# MineralFire-0_3-smd.net
KiCad netlist of a schematic drawn in EAGLE
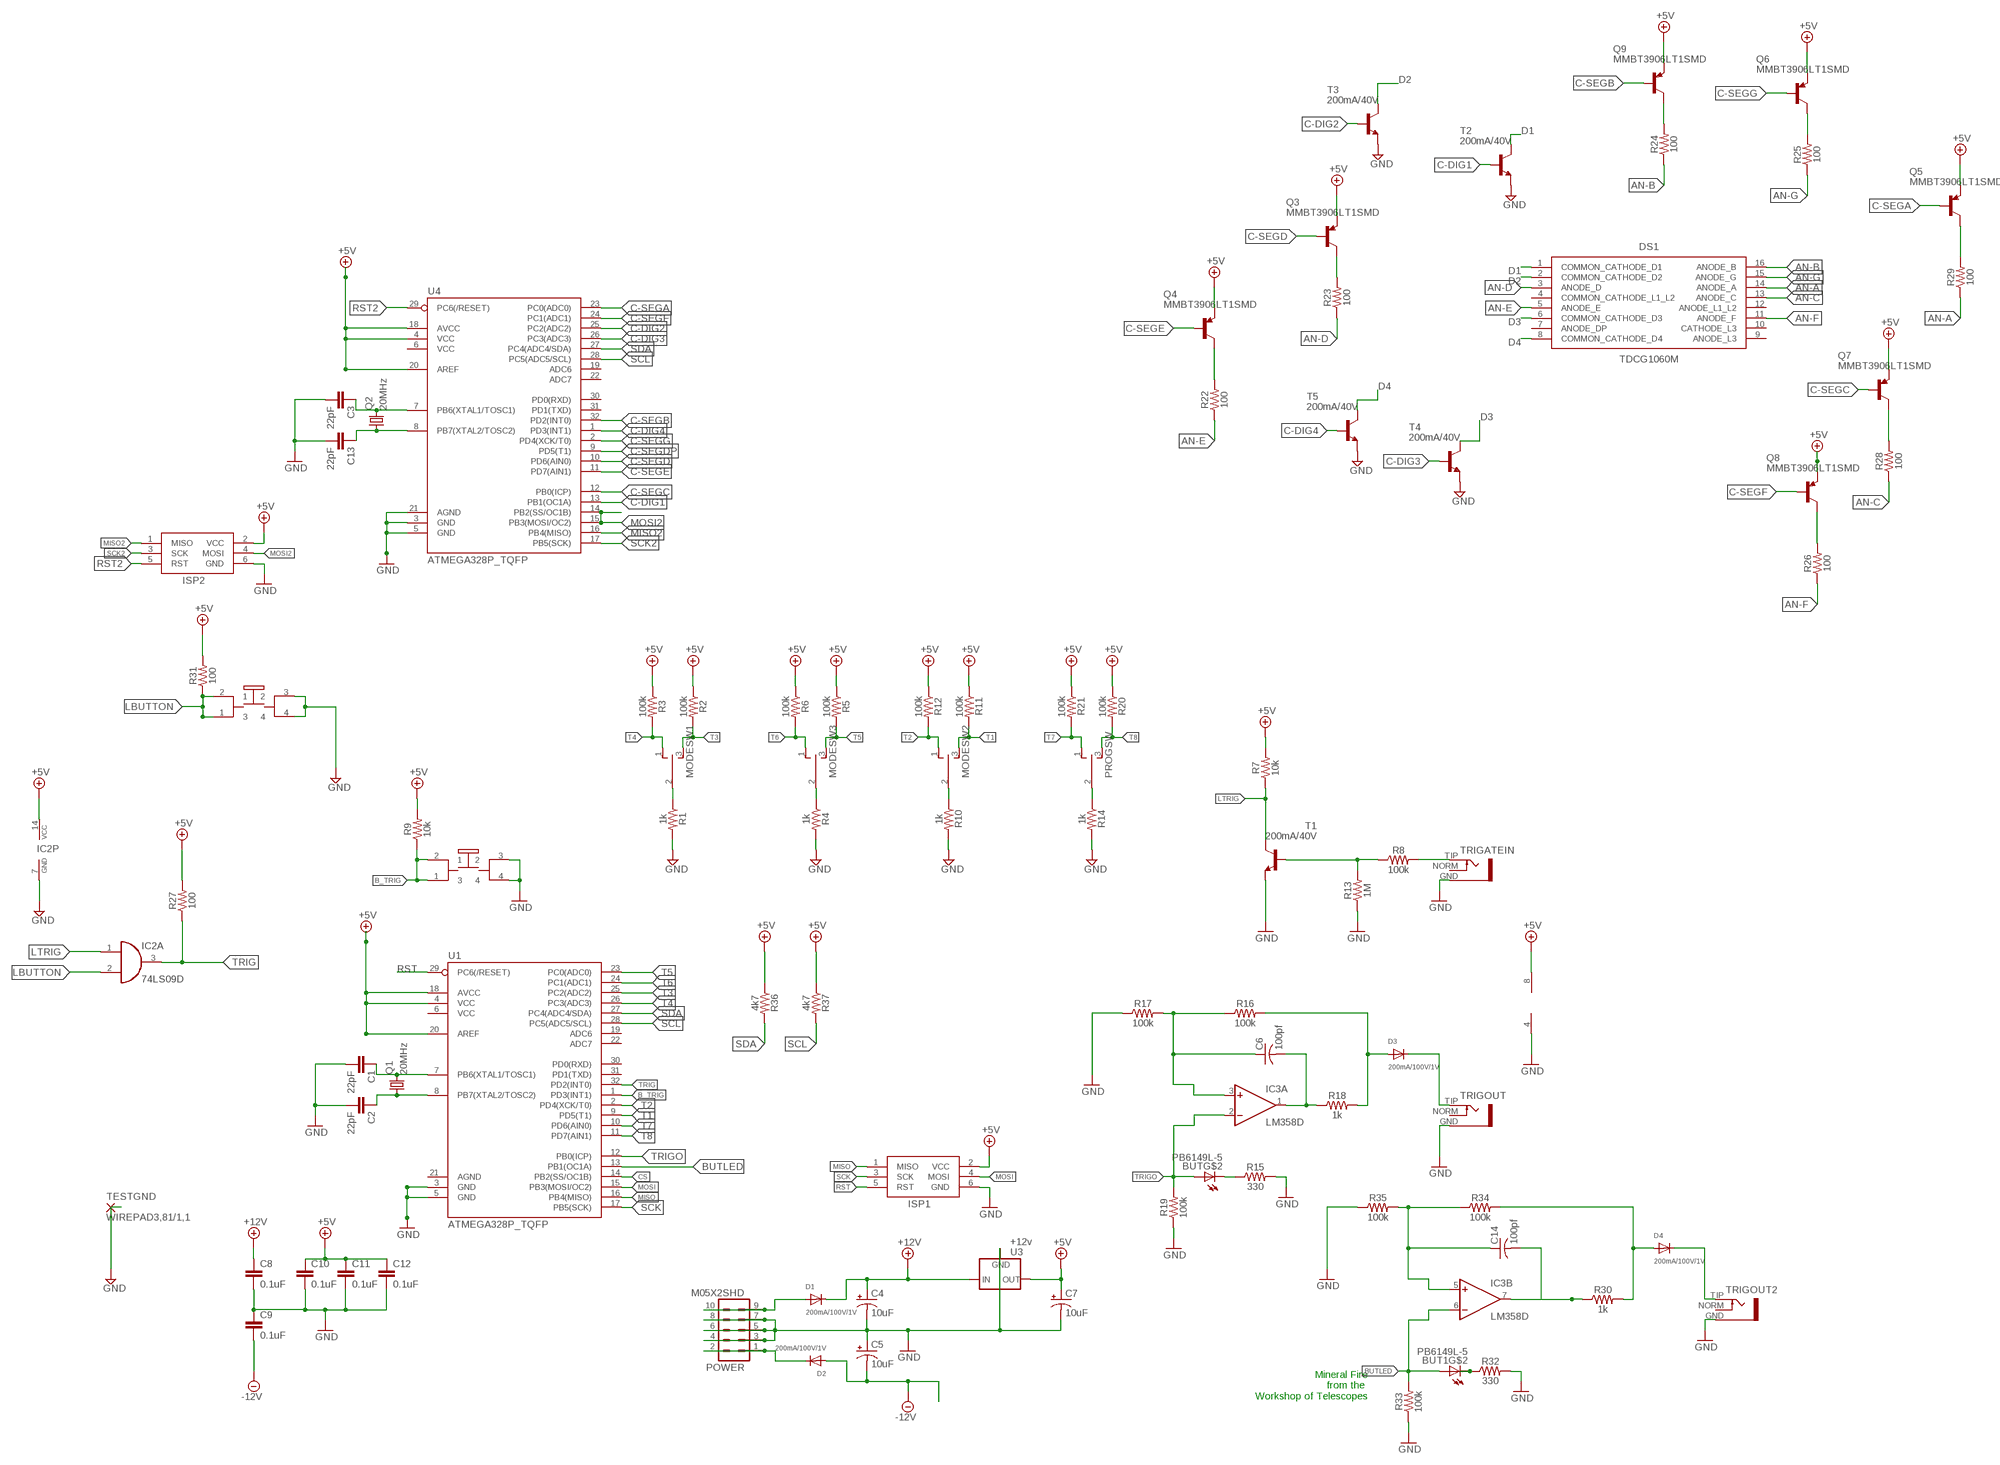
[diagram p0: schematic, sheet 1]

(export (version "E")
  (design (tool "Eeschema 10.0.6"))
  (components
    (comp (ref "BUT")
      (value "PB6149L-5")
      (footprint "eagle-import:PB6149L")
      (libsource (lib "eagle-import") (part "PB6149L-5"))
    )
    (comp (ref "BUT1")
      (value "PB6149L-5")
      (footprint "eagle-import:PB6149L")
      (libsource (lib "eagle-import") (part "PB6149L-5"))
    )
    (comp (ref "C1")
      (value "22pF")
      (footprint "eagle-import:0603")
      (libsource (lib "eagle-import") (part "22PF-0603-50V-5%"))
    )
    (comp (ref "C2")
      (value "22pF")
      (footprint "eagle-import:0603")
      (libsource (lib "eagle-import") (part "22PF-0603-50V-5%"))
    )
    (comp (ref "C3")
      (value "22pF")
      (footprint "eagle-import:0603")
      (libsource (lib "eagle-import") (part "22PF-0603-50V-5%"))
    )
    (comp (ref "C4")
      (value "10uF")
      (footprint "eagle-import:153CLV-0505")
      (libsource (lib "eagle-import") (part "CPOL-US153CLV-0505"))
    )
    (comp (ref "C5")
      (value "10uF")
      (footprint "eagle-import:153CLV-0505")
      (libsource (lib "eagle-import") (part "CPOL-US153CLV-0505"))
    )
    (comp (ref "C6")
      (value "100pf")
      (footprint "eagle-import:C0805K")
      (libsource (lib "eagle-import") (part "C-USC0805K"))
    )
    (comp (ref "C7")
      (value "10uF")
      (footprint "eagle-import:153CLV-0505")
      (libsource (lib "eagle-import") (part "CPOL-US153CLV-0505"))
    )
    (comp (ref "C8")
      (value "0.1uF")
      (footprint "eagle-import:0603")
      (libsource (lib "eagle-import") (part "0.1UF-0603-100V-10%"))
    )
    (comp (ref "C9")
      (value "0.1uF")
      (footprint "eagle-import:0603")
      (libsource (lib "eagle-import") (part "0.1UF-0603-100V-10%"))
    )
    (comp (ref "C10")
      (value "0.1uF")
      (footprint "eagle-import:0603")
      (libsource (lib "eagle-import") (part "0.1UF-0603-100V-10%"))
    )
    (comp (ref "C11")
      (value "0.1uF")
      (footprint "eagle-import:0603")
      (libsource (lib "eagle-import") (part "0.1UF-0603-100V-10%"))
    )
    (comp (ref "C12")
      (value "0.1uF")
      (footprint "eagle-import:0603")
      (libsource (lib "eagle-import") (part "0.1UF-0603-100V-10%"))
    )
    (comp (ref "C13")
      (value "22pF")
      (footprint "eagle-import:0603")
      (libsource (lib "eagle-import") (part "22PF-0603-50V-5%"))
    )
    (comp (ref "C14")
      (value "100pf")
      (footprint "eagle-import:C0805K")
      (libsource (lib "eagle-import") (part "C-USC0805K"))
    )
    (comp (ref "D1")
      (value "200mA/100V/1V")
      (footprint "eagle-import:SMADIODE")
      (libsource (lib "eagle-import") (part "DIODESMA"))
    )
    (comp (ref "D2")
      (value "200mA/100V/1V")
      (footprint "eagle-import:SMADIODE")
      (libsource (lib "eagle-import") (part "DIODESMA"))
    )
    (comp (ref "D3")
      (value "200mA/100V/1V")
      (footprint "eagle-import:SMADIODE")
      (libsource (lib "eagle-import") (part "DIODESMA"))
    )
    (comp (ref "D4")
      (value "200mA/100V/1V")
      (footprint "eagle-import:SMADIODE")
      (libsource (lib "eagle-import") (part "DIODESMA"))
    )
    (comp (ref "DS1")
      (value "TDCG1060M")
      (footprint "eagle-import:DIPS1016W50P254L4020H700Q16N")
      (fields (field (name "RS_PART_NUMBER") "8187530P"))
      (libsource (lib "eagle-import") (part "TDCG1060M"))
    )
    (comp (ref "IC2")
      (value "74LS09D")
      (footprint "eagle-import:SO14")
      (libsource (lib "eagle-import") (part "7409DLS"))
    )
    (comp (ref "IC3")
      (value "LM358D")
      (footprint "eagle-import:SO08")
      (libsource (lib "eagle-import") (part "LM358D"))
    )
    (comp (ref "ISP1")
      (value "AVRISP-6")
      (footprint "eagle-import:AVRISP")
      (libsource (lib "eagle-import") (part "AVRISP-6"))
    )
    (comp (ref "ISP2")
      (value "AVRISP-6")
      (footprint "eagle-import:AVRISP")
      (libsource (lib "eagle-import") (part "AVRISP-6"))
    )
    (comp (ref "MODESW1")
      (value "TOGGLE_ON_OFF_ON")
      (footprint "eagle-import:TOGGLE_ON_OFF_ON")
      (libsource (lib "eagle-import") (part "TOGGLE_ON_OFF_ON"))
    )
    (comp (ref "MODESW2")
      (value "TOGGLE_ON_OFF_ON")
      (footprint "eagle-import:TOGGLE_ON_OFF_ON")
      (libsource (lib "eagle-import") (part "TOGGLE_ON_OFF_ON"))
    )
    (comp (ref "MODESW3")
      (value "TOGGLE_ON_OFF_ON")
      (footprint "eagle-import:TOGGLE_ON_OFF_ON")
      (libsource (lib "eagle-import") (part "TOGGLE_ON_OFF_ON"))
    )
    (comp (ref "POWER")
      (value "M05X2SHD")
      (footprint "eagle-import:2X5-SHROUDED")
      (libsource (lib "eagle-import") (part "M05X2SHD"))
    )
    (comp (ref "PROGSW")
      (value "TOGGLE_ON_OFF_ON")
      (footprint "eagle-import:TOGGLE_ON_OFF_ON")
      (libsource (lib "eagle-import") (part "TOGGLE_ON_OFF_ON"))
    )
    (comp (ref "Q1")
      (value "20MHz")
      (footprint "eagle-import:HC49UP")
      (libsource (lib "eagle-import") (part "CRYSTALHC49UP"))
    )
    (comp (ref "Q2")
      (value "20MHz")
      (footprint "eagle-import:HC49UP")
      (libsource (lib "eagle-import") (part "CRYSTALHC49UP"))
    )
    (comp (ref "Q3")
      (value "MMBT3906LT1SMD")
      (footprint "eagle-import:SOT23-BEC")
      (libsource (lib "eagle-import") (part "MMBT3906SMDLT1"))
    )
    (comp (ref "Q4")
      (value "MMBT3906LT1SMD")
      (footprint "eagle-import:SOT23-BEC")
      (libsource (lib "eagle-import") (part "MMBT3906SMDLT1"))
    )
    (comp (ref "Q5")
      (value "MMBT3906LT1SMD")
      (footprint "eagle-import:SOT23-BEC")
      (libsource (lib "eagle-import") (part "MMBT3906SMDLT1"))
    )
    (comp (ref "Q6")
      (value "MMBT3906LT1SMD")
      (footprint "eagle-import:SOT23-BEC")
      (libsource (lib "eagle-import") (part "MMBT3906SMDLT1"))
    )
    (comp (ref "Q7")
      (value "MMBT3906LT1SMD")
      (footprint "eagle-import:SOT23-BEC")
      (libsource (lib "eagle-import") (part "MMBT3906SMDLT1"))
    )
    (comp (ref "Q8")
      (value "MMBT3906LT1SMD")
      (footprint "eagle-import:SOT23-BEC")
      (libsource (lib "eagle-import") (part "MMBT3906SMDLT1"))
    )
    (comp (ref "Q9")
      (value "MMBT3906LT1SMD")
      (footprint "eagle-import:SOT23-BEC")
      (libsource (lib "eagle-import") (part "MMBT3906SMDLT1"))
    )
    (comp (ref "R1")
      (value "1k")
      (footprint "eagle-import:0603")
      (libsource (lib "eagle-import") (part "1KOHM-0603-1/10W-1%"))
    )
    (comp (ref "R2")
      (value "100k")
      (footprint "eagle-import:0603")
      (libsource (lib "eagle-import") (part "100KOHM-0603-1/10W-1%"))
    )
    (comp (ref "R3")
      (value "100k")
      (footprint "eagle-import:0603")
      (libsource (lib "eagle-import") (part "100KOHM-0603-1/10W-1%"))
    )
    (comp (ref "R4")
      (value "1k")
      (footprint "eagle-import:0603")
      (libsource (lib "eagle-import") (part "1KOHM-0603-1/10W-1%"))
    )
    (comp (ref "R5")
      (value "100k")
      (footprint "eagle-import:0603")
      (libsource (lib "eagle-import") (part "100KOHM-0603-1/10W-1%"))
    )
    (comp (ref "R6")
      (value "100k")
      (footprint "eagle-import:0603")
      (libsource (lib "eagle-import") (part "100KOHM-0603-1/10W-1%"))
    )
    (comp (ref "R7")
      (value "10k")
      (footprint "eagle-import:0603")
      (libsource (lib "eagle-import") (part "10KOHM-0603-1/10W-1%"))
    )
    (comp (ref "R8")
      (value "100k")
      (footprint "eagle-import:0603")
      (libsource (lib "eagle-import") (part "100KOHM-0603-1/10W-1%"))
    )
    (comp (ref "R9")
      (value "10k")
      (footprint "eagle-import:0603")
      (libsource (lib "eagle-import") (part "10KOHM-0603-1/10W-1%"))
    )
    (comp (ref "R10")
      (value "1k")
      (footprint "eagle-import:0603")
      (libsource (lib "eagle-import") (part "1KOHM-0603-1/10W-1%"))
    )
    (comp (ref "R11")
      (value "100k")
      (footprint "eagle-import:0603")
      (libsource (lib "eagle-import") (part "100KOHM-0603-1/10W-1%"))
    )
    (comp (ref "R12")
      (value "100k")
      (footprint "eagle-import:0603")
      (libsource (lib "eagle-import") (part "100KOHM-0603-1/10W-1%"))
    )
    (comp (ref "R13")
      (value "1M")
      (footprint "eagle-import:0603")
      (libsource (lib "eagle-import") (part "1MOHM-0603-1/4W-5%"))
    )
    (comp (ref "R14")
      (value "1k")
      (footprint "eagle-import:0603")
      (libsource (lib "eagle-import") (part "1KOHM-0603-1/10W-1%"))
    )
    (comp (ref "R15")
      (value "330")
      (footprint "eagle-import:0603")
      (libsource (lib "eagle-import") (part "330OHM-0603-1/10W-1%"))
    )
    (comp (ref "R16")
      (value "100k")
      (footprint "eagle-import:0603")
      (libsource (lib "eagle-import") (part "100KOHM-0603-1/10W-1%"))
    )
    (comp (ref "R17")
      (value "100k")
      (footprint "eagle-import:0603")
      (libsource (lib "eagle-import") (part "100KOHM-0603-1/10W-1%"))
    )
    (comp (ref "R18")
      (value "1k")
      (footprint "eagle-import:0603")
      (libsource (lib "eagle-import") (part "1KOHM-0603-1/10W-1%"))
    )
    (comp (ref "R19")
      (value "100k")
      (footprint "eagle-import:0603")
      (libsource (lib "eagle-import") (part "100KOHM-0603-1/10W-1%"))
    )
    (comp (ref "R20")
      (value "100k")
      (footprint "eagle-import:0603")
      (libsource (lib "eagle-import") (part "100KOHM-0603-1/10W-1%"))
    )
    (comp (ref "R21")
      (value "100k")
      (footprint "eagle-import:0603")
      (libsource (lib "eagle-import") (part "100KOHM-0603-1/10W-1%"))
    )
    (comp (ref "R22")
      (value "100")
      (footprint "eagle-import:0603")
      (libsource (lib "eagle-import") (part "100OHM-0603-1/10W-1%"))
    )
    (comp (ref "R23")
      (value "100")
      (footprint "eagle-import:0603")
      (libsource (lib "eagle-import") (part "100OHM-0603-1/10W-1%"))
    )
    (comp (ref "R24")
      (value "100")
      (footprint "eagle-import:0603")
      (libsource (lib "eagle-import") (part "100OHM-0603-1/10W-1%"))
    )
    (comp (ref "R25")
      (value "100")
      (footprint "eagle-import:0603")
      (libsource (lib "eagle-import") (part "100OHM-0603-1/10W-1%"))
    )
    (comp (ref "R26")
      (value "100")
      (footprint "eagle-import:0603")
      (libsource (lib "eagle-import") (part "100OHM-0603-1/10W-1%"))
    )
    (comp (ref "R27")
      (value "100")
      (footprint "eagle-import:0603")
      (libsource (lib "eagle-import") (part "100OHM-0603-1/10W-1%"))
    )
    (comp (ref "R28")
      (value "100")
      (footprint "eagle-import:0603")
      (libsource (lib "eagle-import") (part "100OHM-0603-1/10W-1%"))
    )
    (comp (ref "R29")
      (value "100")
      (footprint "eagle-import:0603")
      (libsource (lib "eagle-import") (part "100OHM-0603-1/10W-1%"))
    )
    (comp (ref "R30")
      (value "1k")
      (footprint "eagle-import:0603")
      (libsource (lib "eagle-import") (part "1KOHM-0603-1/10W-1%"))
    )
    (comp (ref "R31")
      (value "100")
      (footprint "eagle-import:0603")
      (libsource (lib "eagle-import") (part "100OHM-0603-1/10W-1%"))
    )
    (comp (ref "R32")
      (value "330")
      (footprint "eagle-import:0603")
      (libsource (lib "eagle-import") (part "330OHM-0603-1/10W-1%"))
    )
    (comp (ref "R33")
      (value "100k")
      (footprint "eagle-import:0603")
      (libsource (lib "eagle-import") (part "100KOHM-0603-1/10W-1%"))
    )
    (comp (ref "R34")
      (value "100k")
      (footprint "eagle-import:0603")
      (libsource (lib "eagle-import") (part "100KOHM-0603-1/10W-1%"))
    )
    (comp (ref "R35")
      (value "100k")
      (footprint "eagle-import:0603")
      (libsource (lib "eagle-import") (part "100KOHM-0603-1/10W-1%"))
    )
    (comp (ref "R36")
      (value "4k7")
      (footprint "eagle-import:0603")
      (libsource (lib "eagle-import") (part "1KOHM-0603-1/10W-1%"))
    )
    (comp (ref "R37")
      (value "4k7")
      (footprint "eagle-import:0603")
      (libsource (lib "eagle-import") (part "1KOHM-0603-1/10W-1%"))
    )
    (comp (ref "T1")
      (value "200mA/40V")
      (footprint "eagle-import:SOT23-BEC")
      (libsource (lib "eagle-import") (part "-NPN-SOT23-BECMMBT3904LT1"))
    )
    (comp (ref "T2")
      (value "200mA/40V")
      (footprint "eagle-import:SOT23-BEC")
      (libsource (lib "eagle-import") (part "-NPN-SOT23-BECMMBT3904LT1"))
    )
    (comp (ref "T3")
      (value "200mA/40V")
      (footprint "eagle-import:SOT23-BEC")
      (libsource (lib "eagle-import") (part "-NPN-SOT23-BECMMBT3904LT1"))
    )
    (comp (ref "T4")
      (value "200mA/40V")
      (footprint "eagle-import:SOT23-BEC")
      (libsource (lib "eagle-import") (part "-NPN-SOT23-BECMMBT3904LT1"))
    )
    (comp (ref "T5")
      (value "200mA/40V")
      (footprint "eagle-import:SOT23-BEC")
      (libsource (lib "eagle-import") (part "-NPN-SOT23-BECMMBT3904LT1"))
    )
    (comp (ref "TESTGND")
      (value "WIREPAD3,81/1,1")
      (footprint "eagle-import:3,81_1,1")
      (libsource (lib "eagle-import") (part "WIREPAD3,81/1,1"))
    )
    (comp (ref "TRIGATEIN")
      (value "S_JACK")
      (footprint "eagle-import:S_JACK")
      (libsource (lib "eagle-import") (part "S_JACK"))
    )
    (comp (ref "TRIGOUT")
      (value "S_JACK")
      (footprint "eagle-import:S_JACK")
      (libsource (lib "eagle-import") (part "S_JACK"))
    )
    (comp (ref "TRIGOUT2")
      (value "S_JACK")
      (footprint "eagle-import:S_JACK")
      (libsource (lib "eagle-import") (part "S_JACK"))
    )
    (comp (ref "U1")
      (value "ATMEGA328P_TQFP")
      (footprint "eagle-import:TQFP32-08")
      (libsource (lib "eagle-import") (part "ATMEGA328P_TQFP"))
    )
    (comp (ref "U3")
      (value "+12v")
      (footprint "eagle-import:TO-252")
      (libsource (lib "eagle-import") (part "V_REG_78XX7812"))
    )
    (comp (ref "U4")
      (value "ATMEGA328P_TQFP")
      (footprint "eagle-import:TQFP32-08")
      (libsource (lib "eagle-import") (part "ATMEGA328P_TQFP"))
    )
  )
  (nets
    (net (code "1") (name "+5V") (class "Default")
      (node (ref "C10") (pin "1") (pinfunction "1_1") (pintype "passive"))
      (node (ref "C11") (pin "1") (pinfunction "1_1") (pintype "passive"))
      (node (ref "C12") (pin "1") (pinfunction "1_1") (pintype "passive"))
      (node (ref "C7") (pin "+") (pinfunction "+_+") (pintype "passive"))
      (node (ref "IC2") (pin "14") (pinfunction "VCC_14") (pintype "power_in"))
      (node (ref "IC3") (pin "8") (pinfunction "V+_8") (pintype "power_in"))
      (node (ref "ISP1") (pin "2") (pinfunction "VCC_2") (pintype "power_in"))
      (node (ref "ISP2") (pin "2") (pinfunction "VCC_2") (pintype "power_in"))
      (node (ref "Q3") (pin "E") (pinfunction "E_E") (pintype "passive"))
      (node (ref "Q4") (pin "E") (pinfunction "E_E") (pintype "passive"))
      (node (ref "Q5") (pin "E") (pinfunction "E_E") (pintype "passive"))
      (node (ref "Q6") (pin "E") (pinfunction "E_E") (pintype "passive"))
      (node (ref "Q7") (pin "E") (pinfunction "E_E") (pintype "passive"))
      (node (ref "Q8") (pin "E") (pinfunction "E_E") (pintype "passive"))
      (node (ref "Q9") (pin "E") (pinfunction "E_E") (pintype "passive"))
      (node (ref "R11") (pin "1") (pinfunction "1_1") (pintype "passive"))
      (node (ref "R12") (pin "1") (pinfunction "1_1") (pintype "passive"))
      (node (ref "R2") (pin "1") (pinfunction "1_1") (pintype "passive"))
      (node (ref "R20") (pin "1") (pinfunction "1_1") (pintype "passive"))
      (node (ref "R21") (pin "1") (pinfunction "1_1") (pintype "passive"))
      (node (ref "R27") (pin "2") (pinfunction "2_2") (pintype "passive"))
      (node (ref "R3") (pin "1") (pinfunction "1_1") (pintype "passive"))
      (node (ref "R31") (pin "2") (pinfunction "2_2") (pintype "passive"))
      (node (ref "R36") (pin "1") (pinfunction "1_1") (pintype "passive"))
      (node (ref "R37") (pin "1") (pinfunction "1_1") (pintype "passive"))
      (node (ref "R5") (pin "1") (pinfunction "1_1") (pintype "passive"))
      (node (ref "R6") (pin "1") (pinfunction "1_1") (pintype "passive"))
      (node (ref "R7") (pin "2") (pinfunction "2_2") (pintype "passive"))
      (node (ref "R9") (pin "2") (pinfunction "2_2") (pintype "passive"))
      (node (ref "U1") (pin "18") (pinfunction "AVCC_18") (pintype "bidirectional"))
      (node (ref "U1") (pin "20") (pinfunction "AREF_20") (pintype "bidirectional"))
      (node (ref "U1") (pin "4") (pinfunction "VCC_4") (pintype "bidirectional"))
      (node (ref "U3") (pin "2") (pinfunction "OUT_2") (pintype "passive"))
      (node (ref "U4") (pin "18") (pinfunction "AVCC_18") (pintype "bidirectional"))
      (node (ref "U4") (pin "20") (pinfunction "AREF_20") (pintype "bidirectional"))
      (node (ref "U4") (pin "4") (pinfunction "VCC_4") (pintype "bidirectional"))
    )
    (net (code "2") (name "+12V") (class "Default")
      (node (ref "C4") (pin "+") (pinfunction "+_+") (pintype "passive"))
      (node (ref "C8") (pin "1") (pinfunction "1_1") (pintype "passive"))
      (node (ref "D1") (pin "C") (pinfunction "C_C") (pintype "passive"))
      (node (ref "U3") (pin "1") (pinfunction "IN_1") (pintype "input"))
    )
    (net (code "3") (name "-12V") (class "Default")
      (node (ref "C5") (pin "-") (pinfunction "-_-") (pintype "passive"))
      (node (ref "C9") (pin "2") (pinfunction "2_2") (pintype "passive"))
      (node (ref "D2") (pin "A") (pinfunction "A_A") (pintype "passive"))
    )
    (net (code "4") (name "/D1") (class "Default")
      (node (ref "DS1") (pin "1") (pinfunction "COMMON_CATHODE_D1_1") (pintype "input"))
      (node (ref "T2") (pin "C") (pinfunction "C_C") (pintype "passive"))
    )
    (net (code "5") (name "/D2") (class "Default")
      (node (ref "DS1") (pin "2") (pinfunction "COMMON_CATHODE_D2_2") (pintype "input"))
      (node (ref "T3") (pin "C") (pinfunction "C_C") (pintype "passive"))
    )
    (net (code "6") (name "/D3") (class "Default")
      (node (ref "DS1") (pin "6") (pinfunction "COMMON_CATHODE_D3_6") (pintype "input"))
      (node (ref "T4") (pin "C") (pinfunction "C_C") (pintype "passive"))
    )
    (net (code "7") (name "/D4") (class "Default")
      (node (ref "DS1") (pin "8") (pinfunction "COMMON_CATHODE_D4_8") (pintype "input"))
      (node (ref "T5") (pin "C") (pinfunction "C_C") (pintype "passive"))
    )
    (net (code "8") (name "AN-A") (class "Default")
      (node (ref "DS1") (pin "14") (pinfunction "ANODE_A_14") (pintype "input"))
      (node (ref "R29") (pin "1") (pinfunction "1_1") (pintype "passive"))
    )
    (net (code "9") (name "AN-B") (class "Default")
      (node (ref "DS1") (pin "16") (pinfunction "ANODE_B_16") (pintype "input"))
      (node (ref "R24") (pin "1") (pinfunction "1_1") (pintype "passive"))
    )
    (net (code "10") (name "AN-C") (class "Default")
      (node (ref "DS1") (pin "13") (pinfunction "ANODE_C_13") (pintype "input"))
      (node (ref "R28") (pin "1") (pinfunction "1_1") (pintype "passive"))
    )
    (net (code "11") (name "AN-D") (class "Default")
      (node (ref "DS1") (pin "3") (pinfunction "ANODE_D_3") (pintype "input"))
      (node (ref "R23") (pin "1") (pinfunction "1_1") (pintype "passive"))
    )
    (net (code "12") (name "AN-E") (class "Default")
      (node (ref "DS1") (pin "5") (pinfunction "ANODE_E_5") (pintype "input"))
      (node (ref "R22") (pin "1") (pinfunction "1_1") (pintype "passive"))
    )
    (net (code "13") (name "AN-F") (class "Default")
      (node (ref "DS1") (pin "11") (pinfunction "ANODE_F_11") (pintype "input"))
      (node (ref "R26") (pin "1") (pinfunction "1_1") (pintype "passive"))
    )
    (net (code "14") (name "AN-G") (class "Default")
      (node (ref "DS1") (pin "15") (pinfunction "ANODE_G_15") (pintype "input"))
      (node (ref "R25") (pin "1") (pinfunction "1_1") (pintype "passive"))
    )
    (net (code "15") (name "BUTLED") (class "Default")
      (node (ref "BUT1") (pin "A") (pinfunction "A_A") (pintype "passive"))
      (node (ref "IC3") (pin "6") (pinfunction "-IN_6") (pintype "input"))
      (node (ref "R33") (pin "2") (pinfunction "2_2") (pintype "passive"))
      (node (ref "U1") (pin "13") (pinfunction "PB1(OC1A)_13") (pintype "bidirectional"))
    )
    (net (code "16") (name "B_TRIG") (class "Default")
      (node (ref "BUT") (pin "1") (pinfunction "3_1") (pintype "bidirectional"))
      (node (ref "BUT") (pin "2") (pinfunction "1_2") (pintype "bidirectional"))
      (node (ref "R9") (pin "1") (pinfunction "1_1") (pintype "passive"))
      (node (ref "U1") (pin "1") (pinfunction "PD3(INT1)_1") (pintype "bidirectional"))
    )
    (net (code "17") (name "C-DIG1") (class "Default")
      (node (ref "T2") (pin "B") (pinfunction "B_B") (pintype "passive"))
      (node (ref "U4") (pin "13") (pinfunction "PB1(OC1A)_13") (pintype "bidirectional"))
    )
    (net (code "18") (name "C-DIG2") (class "Default")
      (node (ref "T3") (pin "B") (pinfunction "B_B") (pintype "passive"))
      (node (ref "U4") (pin "25") (pinfunction "PC2(ADC2)_25") (pintype "bidirectional"))
    )
    (net (code "19") (name "C-DIG3") (class "Default")
      (node (ref "T4") (pin "B") (pinfunction "B_B") (pintype "passive"))
      (node (ref "U4") (pin "26") (pinfunction "PC3(ADC3)_26") (pintype "bidirectional"))
    )
    (net (code "20") (name "C-DIG4") (class "Default")
      (node (ref "T5") (pin "B") (pinfunction "B_B") (pintype "passive"))
      (node (ref "U4") (pin "1") (pinfunction "PD3(INT1)_1") (pintype "bidirectional"))
    )
    (net (code "21") (name "C-SEGA") (class "Default")
      (node (ref "Q5") (pin "B") (pinfunction "B_B") (pintype "passive"))
      (node (ref "U4") (pin "23") (pinfunction "PC0(ADC0)_23") (pintype "bidirectional"))
    )
    (net (code "22") (name "C-SEGB") (class "Default")
      (node (ref "Q9") (pin "B") (pinfunction "B_B") (pintype "passive"))
      (node (ref "U4") (pin "32") (pinfunction "PD2(INT0)_32") (pintype "bidirectional"))
    )
    (net (code "23") (name "C-SEGC") (class "Default")
      (node (ref "Q7") (pin "B") (pinfunction "B_B") (pintype "passive"))
      (node (ref "U4") (pin "12") (pinfunction "PB0(ICP)_12") (pintype "bidirectional"))
    )
    (net (code "24") (name "C-SEGD") (class "Default")
      (node (ref "Q3") (pin "B") (pinfunction "B_B") (pintype "passive"))
      (node (ref "U4") (pin "10") (pinfunction "PD6(AIN0)_10") (pintype "bidirectional"))
    )
    (net (code "25") (name "C-SEGDP") (class "Default")
      (node (ref "U4") (pin "9") (pinfunction "PD5(T1)_9") (pintype "bidirectional"))
    )
    (net (code "26") (name "C-SEGE") (class "Default")
      (node (ref "Q4") (pin "B") (pinfunction "B_B") (pintype "passive"))
      (node (ref "U4") (pin "11") (pinfunction "PD7(AIN1)_11") (pintype "bidirectional"))
    )
    (net (code "27") (name "C-SEGF") (class "Default")
      (node (ref "Q8") (pin "B") (pinfunction "B_B") (pintype "passive"))
      (node (ref "U4") (pin "24") (pinfunction "PC1(ADC1)_24") (pintype "bidirectional"))
    )
    (net (code "28") (name "C-SEGG") (class "Default")
      (node (ref "Q6") (pin "B") (pinfunction "B_B") (pintype "passive"))
      (node (ref "U4") (pin "2") (pinfunction "PD4(XCK/T0)_2") (pintype "bidirectional"))
    )
    (net (code "29") (name "CS") (class "Default")
      (node (ref "U1") (pin "14") (pinfunction "PB2(SS/OC1B)_14") (pintype "bidirectional"))
    )
    (net (code "30") (name "GND") (class "Default")
      (node (ref "BUT") (pin "3") (pinfunction "2_3") (pintype "bidirectional"))
      (node (ref "BUT") (pin "4") (pinfunction "4_4") (pintype "bidirectional"))
      (node (ref "BUT1") (pin "3") (pinfunction "2_3") (pintype "bidirectional"))
      (node (ref "BUT1") (pin "4") (pinfunction "4_4") (pintype "bidirectional"))
      (node (ref "C1") (pin "2") (pinfunction "2_2") (pintype "passive"))
      (node (ref "C10") (pin "2") (pinfunction "2_2") (pintype "passive"))
      (node (ref "C11") (pin "2") (pinfunction "2_2") (pintype "passive"))
      (node (ref "C12") (pin "2") (pinfunction "2_2") (pintype "passive"))
      (node (ref "C13") (pin "2") (pinfunction "2_2") (pintype "passive"))
      (node (ref "C2") (pin "2") (pinfunction "2_2") (pintype "passive"))
      (node (ref "C3") (pin "2") (pinfunction "2_2") (pintype "passive"))
      (node (ref "C4") (pin "-") (pinfunction "-_-") (pintype "passive"))
      (node (ref "C5") (pin "+") (pinfunction "+_+") (pintype "passive"))
      (node (ref "C7") (pin "-") (pinfunction "-_-") (pintype "passive"))
      (node (ref "C8") (pin "2") (pinfunction "2_2") (pintype "passive"))
      (node (ref "C9") (pin "1") (pinfunction "1_1") (pintype "passive"))
      (node (ref "IC2") (pin "7") (pinfunction "GND_7") (pintype "power_in"))
      (node (ref "IC3") (pin "4") (pinfunction "V-_4") (pintype "power_in"))
      (node (ref "ISP1") (pin "6") (pinfunction "GND_6") (pintype "power_in"))
      (node (ref "ISP2") (pin "6") (pinfunction "GND_6") (pintype "power_in"))
      (node (ref "POWER") (pin "3") (pinfunction "3_3") (pintype "passive"))
      (node (ref "POWER") (pin "4") (pinfunction "4_4") (pintype "passive"))
      (node (ref "POWER") (pin "5") (pinfunction "5_5") (pintype "passive"))
      (node (ref "POWER") (pin "6") (pinfunction "6_6") (pintype "passive"))
      (node (ref "POWER") (pin "7") (pinfunction "7_7") (pintype "passive"))
      (node (ref "POWER") (pin "8") (pinfunction "8_8") (pintype "passive"))
      (node (ref "R1") (pin "2") (pinfunction "2_2") (pintype "passive"))
      (node (ref "R10") (pin "2") (pinfunction "2_2") (pintype "passive"))
      (node (ref "R13") (pin "1") (pinfunction "1_1") (pintype "passive"))
      (node (ref "R14") (pin "2") (pinfunction "2_2") (pintype "passive"))
      (node (ref "R15") (pin "2") (pinfunction "2_2") (pintype "passive"))
      (node (ref "R17") (pin "1") (pinfunction "1_1") (pintype "passive"))
      (node (ref "R19") (pin "1") (pinfunction "1_1") (pintype "passive"))
      (node (ref "R32") (pin "2") (pinfunction "2_2") (pintype "passive"))
      (node (ref "R33") (pin "1") (pinfunction "1_1") (pintype "passive"))
      (node (ref "R35") (pin "1") (pinfunction "1_1") (pintype "passive"))
      (node (ref "R4") (pin "2") (pinfunction "2_2") (pintype "passive"))
      (node (ref "T1") (pin "E") (pinfunction "E_E") (pintype "passive"))
      (node (ref "T2") (pin "E") (pinfunction "E_E") (pintype "passive"))
      (node (ref "T3") (pin "E") (pinfunction "E_E") (pintype "passive"))
      (node (ref "T4") (pin "E") (pinfunction "E_E") (pintype "passive"))
      (node (ref "T5") (pin "E") (pinfunction "E_E") (pintype "passive"))
      (node (ref "TESTGND") (pin "1") (pinfunction "P_1") (pintype "passive"))
      (node (ref "TRIGATEIN") (pin "GND") (pinfunction "GND_GND") (pintype "passive"))
      (node (ref "TRIGOUT") (pin "GND") (pinfunction "GND_GND") (pintype "passive"))
      (node (ref "TRIGOUT2") (pin "GND") (pinfunction "GND_GND") (pintype "passive"))
      (node (ref "U1") (pin "3") (pinfunction "GND_3") (pintype "bidirectional"))
      (node (ref "U1") (pin "5") (pinfunction "GND_5") (pintype "bidirectional"))
      (node (ref "U3") (pin "3") (pinfunction "GND_3") (pintype "input"))
      (node (ref "U4") (pin "21") (pinfunction "AGND_21") (pintype "bidirectional"))
      (node (ref "U4") (pin "3") (pinfunction "GND_3") (pintype "bidirectional"))
      (node (ref "U4") (pin "5") (pinfunction "GND_5") (pintype "bidirectional"))
    )
    (net (code "31") (name "LBUTTON") (class "Default")
      (node (ref "BUT1") (pin "1") (pinfunction "3_1") (pintype "bidirectional"))
      (node (ref "BUT1") (pin "2") (pinfunction "1_2") (pintype "bidirectional"))
      (node (ref "IC2") (pin "2") (pinfunction "I1_2") (pintype "input"))
      (node (ref "R31") (pin "1") (pinfunction "1_1") (pintype "passive"))
    )
    (net (code "32") (name "LTRIG") (class "Default")
      (node (ref "IC2") (pin "1") (pinfunction "I0_1") (pintype "input"))
      (node (ref "R7") (pin "1") (pinfunction "1_1") (pintype "passive"))
      (node (ref "T1") (pin "C") (pinfunction "C_C") (pintype "passive"))
    )
    (net (code "33") (name "MISO") (class "Default")
      (node (ref "ISP1") (pin "1") (pinfunction "MISO_1") (pintype "input"))
      (node (ref "U1") (pin "16") (pinfunction "PB4(MISO)_16") (pintype "bidirectional"))
    )
    (net (code "34") (name "MISO2") (class "Default")
      (node (ref "ISP2") (pin "1") (pinfunction "MISO_1") (pintype "input"))
      (node (ref "U4") (pin "16") (pinfunction "PB4(MISO)_16") (pintype "bidirectional"))
    )
    (net (code "35") (name "MOSI") (class "Default")
      (node (ref "ISP1") (pin "4") (pinfunction "MOSI_4") (pintype "output"))
      (node (ref "U1") (pin "15") (pinfunction "PB3(MOSI/OC2)_15") (pintype "bidirectional"))
    )
    (net (code "36") (name "MOSI2") (class "Default")
      (node (ref "ISP2") (pin "4") (pinfunction "MOSI_4") (pintype "output"))
      (node (ref "U4") (pin "14") (pinfunction "PB2(SS/OC1B)_14") (pintype "bidirectional"))
      (node (ref "U4") (pin "15") (pinfunction "PB3(MOSI/OC2)_15") (pintype "bidirectional"))
    )
    (net (code "37") (name "Net-(BUT1B-C)") (class "Default")
      (node (ref "BUT1") (pin "K") (pinfunction "C_K") (pintype "passive"))
      (node (ref "R32") (pin "1") (pinfunction "1_1") (pintype "passive"))
    )
    (net (code "38") (name "Net-(BUTB-C)") (class "Default")
      (node (ref "BUT") (pin "K") (pinfunction "C_K") (pintype "passive"))
      (node (ref "R15") (pin "1") (pinfunction "1_1") (pintype "passive"))
    )
    (net (code "39") (name "Net-(D1-PadA)") (class "Default")
      (node (ref "D1") (pin "A") (pinfunction "A_A") (pintype "passive"))
      (node (ref "POWER") (pin "10") (pinfunction "10_10") (pintype "passive"))
      (node (ref "POWER") (pin "9") (pinfunction "9_9") (pintype "passive"))
    )
    (net (code "40") (name "Net-(D2-PadC)") (class "Default")
      (node (ref "D2") (pin "C") (pinfunction "C_C") (pintype "passive"))
      (node (ref "POWER") (pin "1") (pinfunction "1_1") (pintype "passive"))
      (node (ref "POWER") (pin "2") (pinfunction "2_2") (pintype "passive"))
    )
    (net (code "41") (name "Net-(D3-PadA)") (class "Default")
      (node (ref "D3") (pin "A") (pinfunction "A_A") (pintype "passive"))
      (node (ref "R16") (pin "2") (pinfunction "2_2") (pintype "passive"))
      (node (ref "R18") (pin "2") (pinfunction "2_2") (pintype "passive"))
    )
    (net (code "42") (name "Net-(D3-PadC)") (class "Default")
      (node (ref "D3") (pin "C") (pinfunction "C_C") (pintype "passive"))
      (node (ref "TRIGOUT") (pin "TIP") (pinfunction "TIP_TIP") (pintype "passive"))
    )
    (net (code "43") (name "Net-(D4-PadA)") (class "Default")
      (node (ref "D4") (pin "A") (pinfunction "A_A") (pintype "passive"))
      (node (ref "R30") (pin "2") (pinfunction "2_2") (pintype "passive"))
    )
    (net (code "44") (name "Net-(D4-PadC)") (class "Default")
      (node (ref "D4") (pin "C") (pinfunction "C_C") (pintype "passive"))
      (node (ref "TRIGOUT2") (pin "TIP") (pinfunction "TIP_TIP") (pintype "passive"))
    )
    (net (code "45") (name "Net-(IC3A-+IN)") (class "Default")
      (node (ref "C6") (pin "1") (pinfunction "1_1") (pintype "passive"))
      (node (ref "IC3") (pin "3") (pinfunction "+IN_3") (pintype "input"))
      (node (ref "R16") (pin "1") (pinfunction "1_1") (pintype "passive"))
      (node (ref "R17") (pin "2") (pinfunction "2_2") (pintype "passive"))
    )
    (net (code "46") (name "Net-(IC3A-OUT)") (class "Default")
      (node (ref "C6") (pin "2") (pinfunction "2_2") (pintype "passive"))
      (node (ref "IC3") (pin "1") (pinfunction "OUT_1") (pintype "output"))
      (node (ref "R18") (pin "1") (pinfunction "1_1") (pintype "passive"))
    )
    (net (code "47") (name "Net-(IC3B-+IN)") (class "Default")
      (node (ref "C14") (pin "1") (pinfunction "1_1") (pintype "passive"))
      (node (ref "IC3") (pin "5") (pinfunction "+IN_5") (pintype "input"))
      (node (ref "R34") (pin "1") (pinfunction "1_1") (pintype "passive"))
      (node (ref "R35") (pin "2") (pinfunction "2_2") (pintype "passive"))
    )
    (net (code "48") (name "Net-(IC3B-OUT)") (class "Default")
      (node (ref "IC3") (pin "7") (pinfunction "OUT_7") (pintype "output"))
      (node (ref "R30") (pin "1") (pinfunction "1_1") (pintype "passive"))
    )
    (net (code "49") (name "Net-(MODESW1-P)") (class "Default")
      (node (ref "MODESW1") (pin "2") (pinfunction "P_2") (pintype "passive"))
      (node (ref "R1") (pin "1") (pinfunction "1_1") (pintype "passive"))
    )
    (net (code "50") (name "Net-(MODESW2-P)") (class "Default")
      (node (ref "MODESW2") (pin "2") (pinfunction "P_2") (pintype "passive"))
      (node (ref "R10") (pin "1") (pinfunction "1_1") (pintype "passive"))
    )
    (net (code "51") (name "Net-(MODESW3-P)") (class "Default")
      (node (ref "MODESW3") (pin "2") (pinfunction "P_2") (pintype "passive"))
      (node (ref "R4") (pin "1") (pinfunction "1_1") (pintype "passive"))
    )
    (net (code "52") (name "Net-(PROGSW-P)") (class "Default")
      (node (ref "PROGSW") (pin "2") (pinfunction "P_2") (pintype "passive"))
      (node (ref "R14") (pin "1") (pinfunction "1_1") (pintype "passive"))
    )
    (net (code "53") (name "Net-(Q3-PadC)") (class "Default")
      (node (ref "Q3") (pin "C") (pinfunction "C_C") (pintype "passive"))
      (node (ref "R23") (pin "2") (pinfunction "2_2") (pintype "passive"))
    )
    (net (code "54") (name "Net-(Q4-PadC)") (class "Default")
      (node (ref "Q4") (pin "C") (pinfunction "C_C") (pintype "passive"))
      (node (ref "R22") (pin "2") (pinfunction "2_2") (pintype "passive"))
    )
    (net (code "55") (name "Net-(Q5-PadC)") (class "Default")
      (node (ref "Q5") (pin "C") (pinfunction "C_C") (pintype "passive"))
      (node (ref "R29") (pin "2") (pinfunction "2_2") (pintype "passive"))
    )
    (net (code "56") (name "Net-(Q6-PadC)") (class "Default")
      (node (ref "Q6") (pin "C") (pinfunction "C_C") (pintype "passive"))
      (node (ref "R25") (pin "2") (pinfunction "2_2") (pintype "passive"))
    )
    (net (code "57") (name "Net-(Q7-PadC)") (class "Default")
      (node (ref "Q7") (pin "C") (pinfunction "C_C") (pintype "passive"))
      (node (ref "R28") (pin "2") (pinfunction "2_2") (pintype "passive"))
    )
    (net (code "58") (name "Net-(Q8-PadC)") (class "Default")
      (node (ref "Q8") (pin "C") (pinfunction "C_C") (pintype "passive"))
      (node (ref "R26") (pin "2") (pinfunction "2_2") (pintype "passive"))
    )
    (net (code "59") (name "Net-(Q9-PadC)") (class "Default")
      (node (ref "Q9") (pin "C") (pinfunction "C_C") (pintype "passive"))
      (node (ref "R24") (pin "2") (pinfunction "2_2") (pintype "passive"))
    )
    (net (code "60") (name "Net-(R8-Pad2)") (class "Default")
      (node (ref "R8") (pin "2") (pinfunction "2_2") (pintype "passive"))
      (node (ref "TRIGATEIN") (pin "TIP") (pinfunction "TIP_TIP") (pintype "passive"))
    )
    (net (code "61") (name "Net-(R13-Pad2)") (class "Default")
      (node (ref "R13") (pin "2") (pinfunction "2_2") (pintype "passive"))
      (node (ref "R8") (pin "1") (pinfunction "1_1") (pintype "passive"))
      (node (ref "T1") (pin "B") (pinfunction "B_B") (pintype "passive"))
    )
    (net (code "62") (name "Net-(U1-PB6(XTAL1{slash}TOSC1))") (class "Default")
      (node (ref "C1") (pin "1") (pinfunction "1_1") (pintype "passive"))
      (node (ref "Q1") (pin "2") (pinfunction "2_2") (pintype "passive"))
      (node (ref "U1") (pin "7") (pinfunction "PB6(XTAL1/TOSC1)_7") (pintype "bidirectional"))
    )
    (net (code "63") (name "Net-(U1-PB7(XTAL2{slash}TOSC2))") (class "Default")
      (node (ref "C2") (pin "1") (pinfunction "1_1") (pintype "passive"))
      (node (ref "Q1") (pin "1") (pinfunction "1_1") (pintype "passive"))
      (node (ref "U1") (pin "8") (pinfunction "PB7(XTAL2/TOSC2)_8") (pintype "bidirectional"))
    )
    (net (code "64") (name "Net-(U4-PB6(XTAL1{slash}TOSC1))") (class "Default")
      (node (ref "C3") (pin "1") (pinfunction "1_1") (pintype "passive"))
      (node (ref "Q2") (pin "2") (pinfunction "2_2") (pintype "passive"))
      (node (ref "U4") (pin "7") (pinfunction "PB6(XTAL1/TOSC1)_7") (pintype "bidirectional"))
    )
    (net (code "65") (name "Net-(U4-PB7(XTAL2{slash}TOSC2))") (class "Default")
      (node (ref "C13") (pin "1") (pinfunction "1_1") (pintype "passive"))
      (node (ref "Q2") (pin "1") (pinfunction "1_1") (pintype "passive"))
      (node (ref "U4") (pin "8") (pinfunction "PB7(XTAL2/TOSC2)_8") (pintype "bidirectional"))
    )
    (net (code "66") (name "RST") (class "Default")
      (node (ref "ISP1") (pin "5") (pinfunction "RST_5") (pintype "output"))
      (node (ref "U1") (pin "29") (pinfunction "PC6(/RESET)_29") (pintype "bidirectional"))
    )
    (net (code "67") (name "RST2") (class "Default")
      (node (ref "ISP2") (pin "5") (pinfunction "RST_5") (pintype "output"))
      (node (ref "U4") (pin "29") (pinfunction "PC6(/RESET)_29") (pintype "bidirectional"))
    )
    (net (code "68") (name "SCK") (class "Default")
      (node (ref "ISP1") (pin "3") (pinfunction "SCK_3") (pintype "output"))
      (node (ref "U1") (pin "17") (pinfunction "PB5(SCK)_17") (pintype "bidirectional"))
    )
    (net (code "69") (name "SCK2") (class "Default")
      (node (ref "ISP2") (pin "3") (pinfunction "SCK_3") (pintype "output"))
      (node (ref "U4") (pin "17") (pinfunction "PB5(SCK)_17") (pintype "bidirectional"))
    )
    (net (code "70") (name "SCL") (class "Default")
      (node (ref "R37") (pin "2") (pinfunction "2_2") (pintype "passive"))
      (node (ref "U1") (pin "28") (pinfunction "PC5(ADC5/SCL)_28") (pintype "bidirectional"))
      (node (ref "U4") (pin "28") (pinfunction "PC5(ADC5/SCL)_28") (pintype "bidirectional"))
    )
    (net (code "71") (name "SDA") (class "Default")
      (node (ref "R36") (pin "2") (pinfunction "2_2") (pintype "passive"))
      (node (ref "U1") (pin "27") (pinfunction "PC4(ADC4/SDA)_27") (pintype "bidirectional"))
      (node (ref "U4") (pin "27") (pinfunction "PC4(ADC4/SDA)_27") (pintype "bidirectional"))
    )
    (net (code "72") (name "T1") (class "Default")
      (node (ref "MODESW2") (pin "3") (pinfunction "S_3") (pintype "passive"))
      (node (ref "R11") (pin "2") (pinfunction "2_2") (pintype "passive"))
      (node (ref "U1") (pin "9") (pinfunction "PD5(T1)_9") (pintype "bidirectional"))
    )
    (net (code "73") (name "T2") (class "Default")
      (node (ref "MODESW2") (pin "1") (pinfunction "O_1") (pintype "passive"))
      (node (ref "R12") (pin "2") (pinfunction "2_2") (pintype "passive"))
      (node (ref "U1") (pin "2") (pinfunction "PD4(XCK/T0)_2") (pintype "bidirectional"))
    )
    (net (code "74") (name "T3") (class "Default")
      (node (ref "MODESW1") (pin "3") (pinfunction "S_3") (pintype "passive"))
      (node (ref "R2") (pin "2") (pinfunction "2_2") (pintype "passive"))
      (node (ref "U1") (pin "25") (pinfunction "PC2(ADC2)_25") (pintype "bidirectional"))
    )
    (net (code "75") (name "T4") (class "Default")
      (node (ref "MODESW1") (pin "1") (pinfunction "O_1") (pintype "passive"))
      (node (ref "R3") (pin "2") (pinfunction "2_2") (pintype "passive"))
      (node (ref "U1") (pin "26") (pinfunction "PC3(ADC3)_26") (pintype "bidirectional"))
    )
    (net (code "76") (name "T5") (class "Default")
      (node (ref "MODESW3") (pin "3") (pinfunction "S_3") (pintype "passive"))
      (node (ref "R5") (pin "2") (pinfunction "2_2") (pintype "passive"))
      (node (ref "U1") (pin "23") (pinfunction "PC0(ADC0)_23") (pintype "bidirectional"))
    )
    (net (code "77") (name "T6") (class "Default")
      (node (ref "MODESW3") (pin "1") (pinfunction "O_1") (pintype "passive"))
      (node (ref "R6") (pin "2") (pinfunction "2_2") (pintype "passive"))
      (node (ref "U1") (pin "24") (pinfunction "PC1(ADC1)_24") (pintype "bidirectional"))
    )
    (net (code "78") (name "T7") (class "Default")
      (node (ref "PROGSW") (pin "1") (pinfunction "O_1") (pintype "passive"))
      (node (ref "R21") (pin "2") (pinfunction "2_2") (pintype "passive"))
      (node (ref "U1") (pin "10") (pinfunction "PD6(AIN0)_10") (pintype "bidirectional"))
    )
    (net (code "79") (name "T8") (class "Default")
      (node (ref "PROGSW") (pin "3") (pinfunction "S_3") (pintype "passive"))
      (node (ref "R20") (pin "2") (pinfunction "2_2") (pintype "passive"))
      (node (ref "U1") (pin "11") (pinfunction "PD7(AIN1)_11") (pintype "bidirectional"))
    )
    (net (code "80") (name "TRIG") (class "Default")
      (node (ref "IC2") (pin "3") (pinfunction "O_3") (pintype "open_collector"))
      (node (ref "R27") (pin "1") (pinfunction "1_1") (pintype "passive"))
      (node (ref "U1") (pin "32") (pinfunction "PD2(INT0)_32") (pintype "bidirectional"))
    )
    (net (code "81") (name "TRIGO") (class "Default")
      (node (ref "BUT") (pin "A") (pinfunction "A_A") (pintype "passive"))
      (node (ref "IC3") (pin "2") (pinfunction "-IN_2") (pintype "input"))
      (node (ref "R19") (pin "2") (pinfunction "2_2") (pintype "passive"))
      (node (ref "U1") (pin "12") (pinfunction "PB0(ICP)_12") (pintype "bidirectional"))
    )
    (net (code "82") (name "unconnected-(C14-Pad2)") (class "Default")
      (node (ref "C14") (pin "2") (pinfunction "2_2") (pintype "passive"))
    )
    (net (code "83") (name "unconnected-(DS1-ANODE_DP-Pad7)") (class "Default")
      (node (ref "DS1") (pin "7") (pinfunction "ANODE_DP_7") (pintype "input"))
    )
    (net (code "84") (name "unconnected-(DS1-ANODE_L1_L2-Pad12)") (class "Default")
      (node (ref "DS1") (pin "12") (pinfunction "ANODE_L1_L2_12") (pintype "input"))
    )
    (net (code "85") (name "unconnected-(DS1-ANODE_L3-Pad9)") (class "Default")
      (node (ref "DS1") (pin "9") (pinfunction "ANODE_L3_9") (pintype "input"))
    )
    (net (code "86") (name "unconnected-(DS1-CATHODE_L3-Pad10)") (class "Default")
      (node (ref "DS1") (pin "10") (pinfunction "CATHODE_L3_10") (pintype "input"))
    )
    (net (code "87") (name "unconnected-(DS1-COMMON_CATHODE_L1_L2-Pad4)") (class "Default")
      (node (ref "DS1") (pin "4") (pinfunction "COMMON_CATHODE_L1_L2_4") (pintype "input"))
    )
    (net (code "88") (name "unconnected-(R34-Pad2)") (class "Default")
      (node (ref "R34") (pin "2") (pinfunction "2_2") (pintype "passive"))
    )
    (net (code "89") (name "unconnected-(TRIGATEIN-PadNORM)") (class "Default")
      (node (ref "TRIGATEIN") (pin "NORM") (pinfunction "NORM_NORM") (pintype "passive"))
    )
    (net (code "90") (name "unconnected-(TRIGOUT-PadNORM)") (class "Default")
      (node (ref "TRIGOUT") (pin "NORM") (pinfunction "NORM_NORM") (pintype "passive"))
    )
    (net (code "91") (name "unconnected-(TRIGOUT2-PadNORM)") (class "Default")
      (node (ref "TRIGOUT2") (pin "NORM") (pinfunction "NORM_NORM") (pintype "passive"))
    )
    (net (code "92") (name "unconnected-(U1-ADC6-Pad19)") (class "Default")
      (node (ref "U1") (pin "19") (pinfunction "ADC6_19") (pintype "bidirectional"))
    )
    (net (code "93") (name "unconnected-(U1-ADC7-Pad22)") (class "Default")
      (node (ref "U1") (pin "22") (pinfunction "ADC7_22") (pintype "bidirectional"))
    )
    (net (code "94") (name "unconnected-(U1-AGND-Pad21)") (class "Default")
      (node (ref "U1") (pin "21") (pinfunction "AGND_21") (pintype "bidirectional"))
    )
    (net (code "95") (name "unconnected-(U1-PD0(RXD)-Pad30)") (class "Default")
      (node (ref "U1") (pin "30") (pinfunction "PD0(RXD)_30") (pintype "bidirectional"))
    )
    (net (code "96") (name "unconnected-(U1-PD1(TXD)-Pad31)") (class "Default")
      (node (ref "U1") (pin "31") (pinfunction "PD1(TXD)_31") (pintype "bidirectional"))
    )
    (net (code "97") (name "unconnected-(U1-VCC-Pad6)") (class "Default")
      (node (ref "U1") (pin "6") (pinfunction "VCC_6") (pintype "bidirectional"))
    )
    (net (code "98") (name "unconnected-(U4-ADC6-Pad19)") (class "Default")
      (node (ref "U4") (pin "19") (pinfunction "ADC6_19") (pintype "bidirectional"))
    )
    (net (code "99") (name "unconnected-(U4-ADC7-Pad22)") (class "Default")
      (node (ref "U4") (pin "22") (pinfunction "ADC7_22") (pintype "bidirectional"))
    )
    (net (code "100") (name "unconnected-(U4-PD0(RXD)-Pad30)") (class "Default")
      (node (ref "U4") (pin "30") (pinfunction "PD0(RXD)_30") (pintype "bidirectional"))
    )
    (net (code "101") (name "unconnected-(U4-PD1(TXD)-Pad31)") (class "Default")
      (node (ref "U4") (pin "31") (pinfunction "PD1(TXD)_31") (pintype "bidirectional"))
    )
    (net (code "102") (name "unconnected-(U4-VCC-Pad6)") (class "Default")
      (node (ref "U4") (pin "6") (pinfunction "VCC_6") (pintype "bidirectional"))
    )
  )
)
